# IMD.net
KiCad netlist of a schematic drawn in Altium Designer
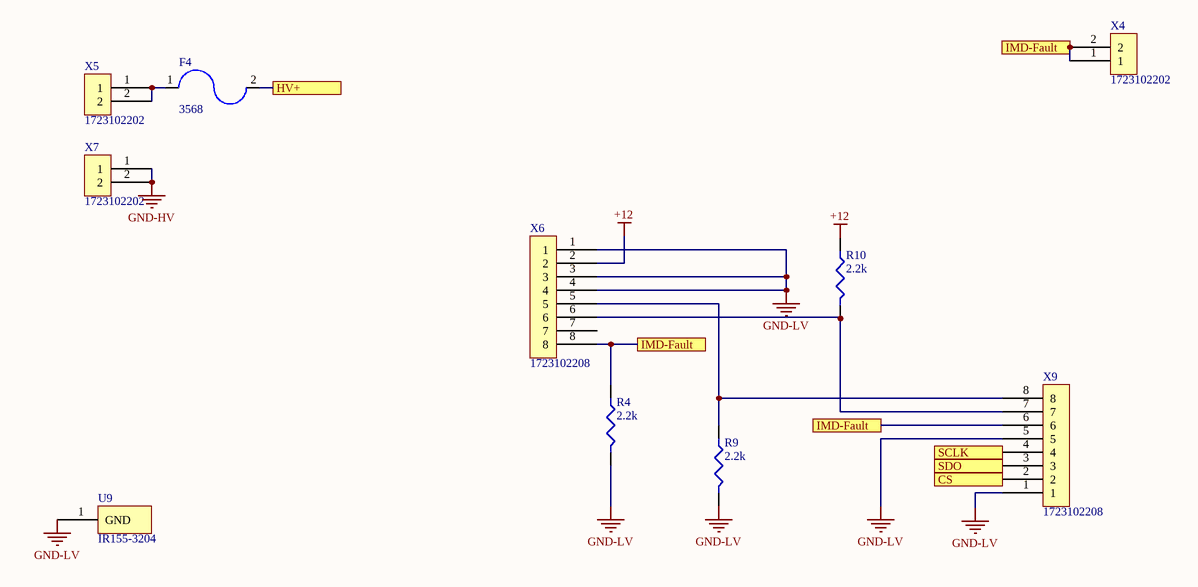
[diagram p0: IMD.SchDoc]

(export (version "E")
  (design (tool "Eeschema 10.0.6"))
  (components
    (comp (ref "F4")
      (value "3568")
      (footprint "FUSE_MINI_HOLDER")
      (description "FUSE HOLDER MINI AUTO PC")
      (fields (field (name "MANUFACTURER") "Keystone Electronics") (field (name "VOLTAGE") "500V"))
      (libsource (lib "PHANTOM_LIBRARY") (part "3568"))
    )
    (comp (ref "R4")
      (value "2.2k")
      (footprint "R0805")
      (description "RES SMD 2.2K OHM 5% 1/8W")
      (fields
        (field (name "MANUFACTURER") "Yageo")
        (field (name "MANUFACTURER PART NUMBER") "RC0805JR-072K2L")
      )
      (libsource (lib "PHANTOM_LIBRARY") (part "RC0805JR-072K2L"))
    )
    (comp (ref "R9")
      (value "2.2k")
      (footprint "R0805")
      (description "RES SMD 2.2K OHM 5% 1/8W")
      (fields
        (field (name "MANUFACTURER") "Yageo")
        (field (name "MANUFACTURER PART NUMBER") "RC0805JR-072K2L")
      )
      (libsource (lib "PHANTOM_LIBRARY") (part "RC0805JR-072K2L"))
    )
    (comp (ref "R10")
      (value "2.2k")
      (footprint "R0805")
      (description "RES SMD 2.2K OHM 5% 1/8W")
      (fields
        (field (name "MANUFACTURER") "Yageo")
        (field (name "MANUFACTURER PART NUMBER") "RC0805JR-072K2L")
      )
      (libsource (lib "PHANTOM_LIBRARY") (part "RC0805JR-072K2L"))
    )
    (comp (ref "U9")
      (value "IR155-3204")
      (footprint "IR155-3204")
      (description "IMD")
      (fields (field (name "MANUFACTURER") "Bender"))
      (libsource (lib "PHANTOM_LIBRARY") (part "IR155-3204"))
    )
    (comp (ref "X4")
      (value "1723102202")
      (footprint "Molex2Pin")
      (description "CONN HEADER R/A 2POS 3.5MM")
      (fields (field (name "MANUFACTURER") "Molex"))
      (libsource (lib "") (part "1723102202_1"))
    )
    (comp (ref "X5")
      (value "1723102202")
      (footprint "Molex2Pin")
      (description "CONN HEADER R/A 2POS 3.5MM")
      (fields (field (name "MANUFACTURER") "Molex"))
      (libsource (lib "PHANTOM_LIBRARY") (part "1723102202"))
    )
    (comp (ref "X6")
      (value "1723102208")
      (footprint "Molex8Pin")
      (description "CONN HEADER R/A 8POS 3.5MM")
      (fields (field (name "MANUFACTURER") "Molex"))
      (libsource (lib "PHANTOM_LIBRARY") (part "1723102208"))
    )
    (comp (ref "X7")
      (value "1723102202")
      (footprint "Molex2Pin")
      (description "CONN HEADER R/A 2POS 3.5MM")
      (fields (field (name "MANUFACTURER") "Molex"))
      (libsource (lib "PHANTOM_LIBRARY") (part "1723102202"))
    )
    (comp (ref "X9")
      (value "1723102208")
      (footprint "Molex8Pin")
      (description "CONN HEADER R/A 8POS 3.5MM")
      (fields (field (name "MANUFACTURER") "Molex"))
      (libsource (lib "") (part "1723102208_1"))
    )
  )
  (nets
    (net (code "1") (name "+12") (class "Default")
      (node (ref "R10") (pin "1") (pinfunction "1_1") (pintype "passive"))
      (node (ref "X6") (pin "2") (pinfunction "2_2") (pintype "passive"))
    )
    (net (code "2") (name "/CS") (class "Default")
      (node (ref "X9") (pin "2") (pinfunction "2_2") (pintype "passive"))
    )
    (net (code "3") (name "/HV+") (class "Default")
      (node (ref "F4") (pin "2") (pinfunction "2_2") (pintype "passive"))
    )
    (net (code "4") (name "/IMD-Fault") (class "Default")
      (node (ref "R4") (pin "1") (pinfunction "1_1") (pintype "passive"))
      (node (ref "X4") (pin "1") (pinfunction "1_1") (pintype "passive"))
      (node (ref "X4") (pin "2") (pinfunction "2_2") (pintype "passive"))
      (node (ref "X6") (pin "8") (pinfunction "8_8") (pintype "passive"))
      (node (ref "X9") (pin "6") (pinfunction "6_6") (pintype "passive"))
    )
    (net (code "5") (name "/SCLK") (class "Default")
      (node (ref "X9") (pin "4") (pinfunction "4_4") (pintype "passive"))
    )
    (net (code "6") (name "/SDO") (class "Default")
      (node (ref "X9") (pin "3") (pinfunction "3_3") (pintype "passive"))
    )
    (net (code "7") (name "GND-HV") (class "Default")
      (node (ref "X7") (pin "1") (pinfunction "1_1") (pintype "passive"))
      (node (ref "X7") (pin "2") (pinfunction "2_2") (pintype "passive"))
    )
    (net (code "8") (name "GND-LV") (class "Default")
      (node (ref "R4") (pin "2") (pinfunction "2_2") (pintype "passive"))
      (node (ref "R9") (pin "2") (pinfunction "2_2") (pintype "passive"))
      (node (ref "U9") (pin "1") (pinfunction "GND_1") (pintype "passive"))
      (node (ref "X6") (pin "1") (pinfunction "1_1") (pintype "passive"))
      (node (ref "X6") (pin "3") (pinfunction "3_3") (pintype "passive"))
      (node (ref "X6") (pin "4") (pinfunction "4_4") (pintype "passive"))
      (node (ref "X9") (pin "1") (pinfunction "1_1") (pintype "passive"))
      (node (ref "X9") (pin "5") (pinfunction "5_5") (pintype "passive"))
    )
    (net (code "9") (name "Net-(F4-Pad1)") (class "Default")
      (node (ref "F4") (pin "1") (pinfunction "1_1") (pintype "passive"))
      (node (ref "X5") (pin "1") (pinfunction "1_1") (pintype "passive"))
      (node (ref "X5") (pin "2") (pinfunction "2_2") (pintype "passive"))
    )
    (net (code "10") (name "Net-(R9-Pad1)") (class "Default")
      (node (ref "R9") (pin "1") (pinfunction "1_1") (pintype "passive"))
      (node (ref "X6") (pin "5") (pinfunction "5_5") (pintype "passive"))
      (node (ref "X9") (pin "8") (pinfunction "8_8") (pintype "passive"))
    )
    (net (code "11") (name "Net-(R10-Pad2)") (class "Default")
      (node (ref "R10") (pin "2") (pinfunction "2_2") (pintype "passive"))
      (node (ref "X6") (pin "6") (pinfunction "6_6") (pintype "passive"))
      (node (ref "X9") (pin "7") (pinfunction "7_7") (pintype "passive"))
    )
    (net (code "12") (name "unconnected-(X6-Pad7)") (class "Default")
      (node (ref "X6") (pin "7") (pinfunction "7_7") (pintype "passive"))
    )
  )
)
